# MainSchematic.net
KiCad netlist of a schematic drawn in Altium Designer
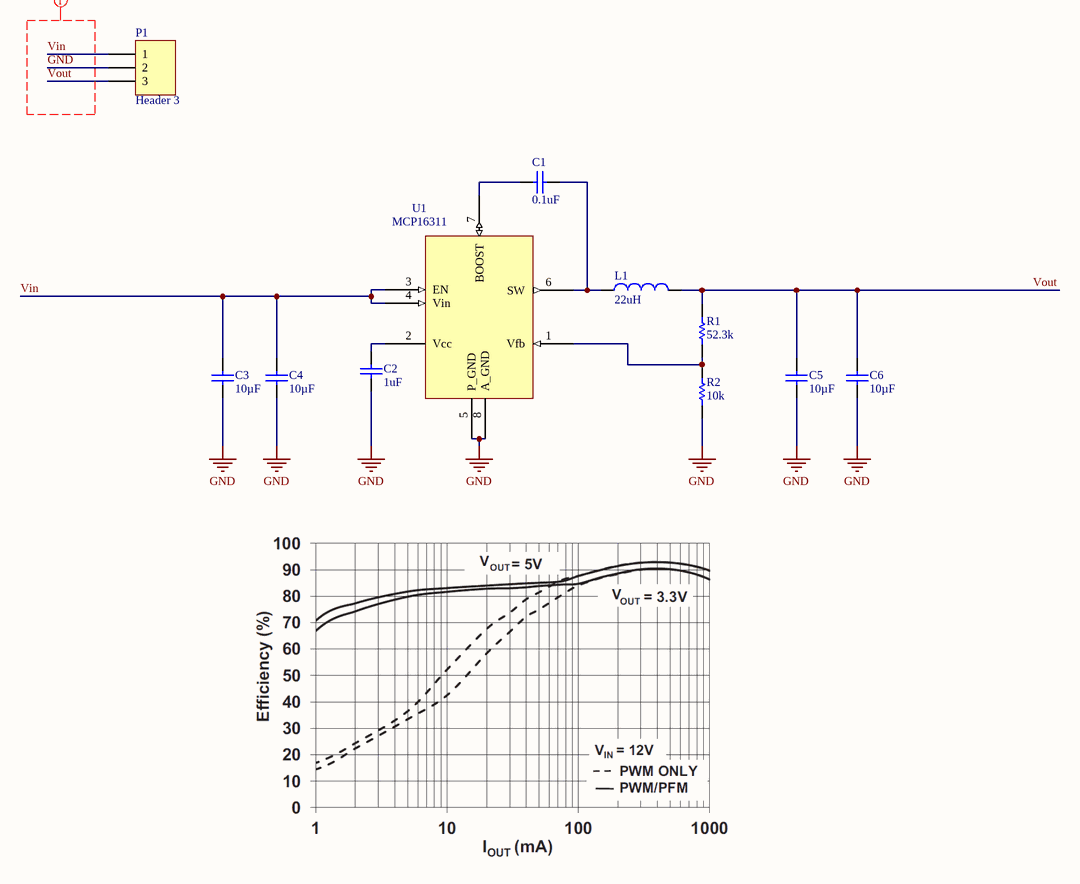
[diagram p0: MainSchematic.SchDoc]

(export (version "E")
  (design (tool "Eeschema 10.0.6"))
  (components
    (comp (ref "C1")
      (value "0.1uF")
      (footprint "CAPC1005X55X30NL05T10")
      (fields (field (name "MFG") "Kemet"))
      (libsource (lib "Altium Content Vault") (part "CAP"))
    )
    (comp (ref "C2")
      (value "1uF")
      (footprint "CAPC1608X90X35LL15T15")
      (fields (field (name "MFG") "Kemet"))
      (libsource (lib "Altium Content Vault") (part "CAP"))
    )
    (comp (ref "C3")
      (value "10µF")
      (footprint "CAPC1608X90X35NL10T15")
      (fields (field (name "MFG") "Murata"))
      (libsource (lib "Altium Content Vault") (part "CAP"))
    )
    (comp (ref "C4")
      (value "10µF")
      (footprint "CAPC1608X90X35NL10T15")
      (fields (field (name "MFG") "Murata"))
      (libsource (lib "Altium Content Vault") (part "CAP"))
    )
    (comp (ref "C5")
      (value "10µF")
      (footprint "CAPC1005X70X10NL05")
      (description "Chip Capacitor, 10 uF, +/- 20%, -55 to 85 degC, 0402 (1005 Metric), RoHS, Tape and Reel")
      (fields (field (name "TOLERANCE") "±20%") (field (name "MANUFACTURER") "TDK"))
      (libsource (lib "Altium Content Vault") (part "CAP-NP-2"))
    )
    (comp (ref "C6")
      (value "10µF")
      (footprint "CAPC1005X70X10NL05")
      (description "Chip Capacitor, 10 uF, +/- 20%, -55 to 85 degC, 0402 (1005 Metric), RoHS, Tape and Reel")
      (fields (field (name "TOLERANCE") "±20%") (field (name "MANUFACTURER") "TDK"))
      (libsource (lib "Altium Content Vault") (part "CAP-NP-2"))
    )
    (comp (ref "L1")
      (value "22uH")
      (footprint "Coil CMS TDK VLCF")
      (description "Inductance bobinée CMS, 22 μH, 1.1A max , dimensions 5.3 x 5 x 2mm, Blindé, série VLCF")
      (fields (field (name "MFG") "TDK"))
      (libsource (lib "LibrairieSchema") (part "Ind 22uH 1.1A CMS"))
    )
    (comp (ref "P1")
      (value "Header 3")
      (footprint "HDR1X3")
      (description "Header, 3-Pin")
      (fields (field (name "PUBLISHER") "Altium Limited"))
      (libsource (lib "Miscellaneous Connectors") (part "Header 3"))
    )
    (comp (ref "R1")
      (value "52.3k")
      (footprint "RESC0402(1005)_N")
      (description "52K3 0.063W 1% 0402 (1005 Metric)  SMD")
      (fields (field (name "POWER") "0.063 W") (field (name "TOLERANCE") "1 %"))
      (libsource (lib "Altium Content Vault") (part "RES"))
    )
    (comp (ref "R2")
      (value "10k")
      (footprint "RESC0402(1005)_N")
      (description "10K 0.063W 1% 0402 (1005 Metric)  SMD")
      (fields (field (name "TOLERANCE") "1 %") (field (name "POWER") "0.063 W"))
      (libsource (lib "Altium Content Vault") (part "RES"))
    )
    (comp (ref "U1")
      (value "MCP16311")
      (footprint "TDFN-MN8")
      (description "30V Input, 1A Output, High-Efficiency,Integrated Synchronous Switch Step-Down Regulator")
      (fields (field (name "MFG") "Microchip"))
      (libsource (lib "LibrairieSchema") (part "MCP16311"))
    )
  )
  (nets
    (net (code "1") (name "/Vin") (class "Default")
      (node (ref "C3") (pin "1") (pinfunction "1_1") (pintype "passive"))
      (node (ref "C4") (pin "1") (pinfunction "1_1") (pintype "passive"))
      (node (ref "P1") (pin "1") (pinfunction "1_1") (pintype "passive"))
      (node (ref "U1") (pin "3") (pinfunction "EN_3") (pintype "input"))
      (node (ref "U1") (pin "4") (pinfunction "Vin_4") (pintype "input"))
    )
    (net (code "2") (name "/Vout") (class "Default")
      (node (ref "C5") (pin "2") (pinfunction "2_2") (pintype "passive"))
      (node (ref "C6") (pin "2") (pinfunction "2_2") (pintype "passive"))
      (node (ref "L1") (pin "2") (pinfunction "2_2") (pintype "passive"))
      (node (ref "P1") (pin "3") (pinfunction "3_3") (pintype "passive"))
      (node (ref "R1") (pin "2") (pinfunction "2_2") (pintype "passive"))
    )
    (net (code "3") (name "GND") (class "Default")
      (node (ref "C2") (pin "1") (pinfunction "1_1") (pintype "passive"))
      (node (ref "C3") (pin "2") (pinfunction "2_2") (pintype "passive"))
      (node (ref "C4") (pin "2") (pinfunction "2_2") (pintype "passive"))
      (node (ref "C5") (pin "1") (pinfunction "1_1") (pintype "passive"))
      (node (ref "C6") (pin "1") (pinfunction "1_1") (pintype "passive"))
      (node (ref "P1") (pin "2") (pinfunction "2_2") (pintype "passive"))
      (node (ref "R2") (pin "1") (pinfunction "1_1") (pintype "passive"))
      (node (ref "U1") (pin "5") (pinfunction "P_GND_5") (pintype "power_in"))
      (node (ref "U1") (pin "8") (pinfunction "A_GND_8") (pintype "power_in"))
    )
    (net (code "4") (name "Net-(U1-BOOST)") (class "Default")
      (node (ref "C1") (pin "1") (pinfunction "1_1") (pintype "passive"))
      (node (ref "U1") (pin "7") (pinfunction "BOOST_7") (pintype "bidirectional"))
    )
    (net (code "5") (name "Net-(U1-SW)") (class "Default")
      (node (ref "C1") (pin "2") (pinfunction "2_2") (pintype "passive"))
      (node (ref "L1") (pin "1") (pinfunction "1_1") (pintype "passive"))
      (node (ref "U1") (pin "6") (pinfunction "SW_6") (pintype "output"))
    )
    (net (code "6") (name "Net-(U1-Vcc)") (class "Default")
      (node (ref "C2") (pin "2") (pinfunction "2_2") (pintype "passive"))
      (node (ref "U1") (pin "2") (pinfunction "Vcc_2") (pintype "power_in"))
    )
    (net (code "7") (name "Net-(U1-Vfb)") (class "Default")
      (node (ref "R1") (pin "1") (pinfunction "1_1") (pintype "passive"))
      (node (ref "R2") (pin "2") (pinfunction "2_2") (pintype "passive"))
      (node (ref "U1") (pin "1") (pinfunction "Vfb_1") (pintype "input"))
    )
  )
)
